# Slave.net
KiCad netlist of a schematic drawn in EAGLE
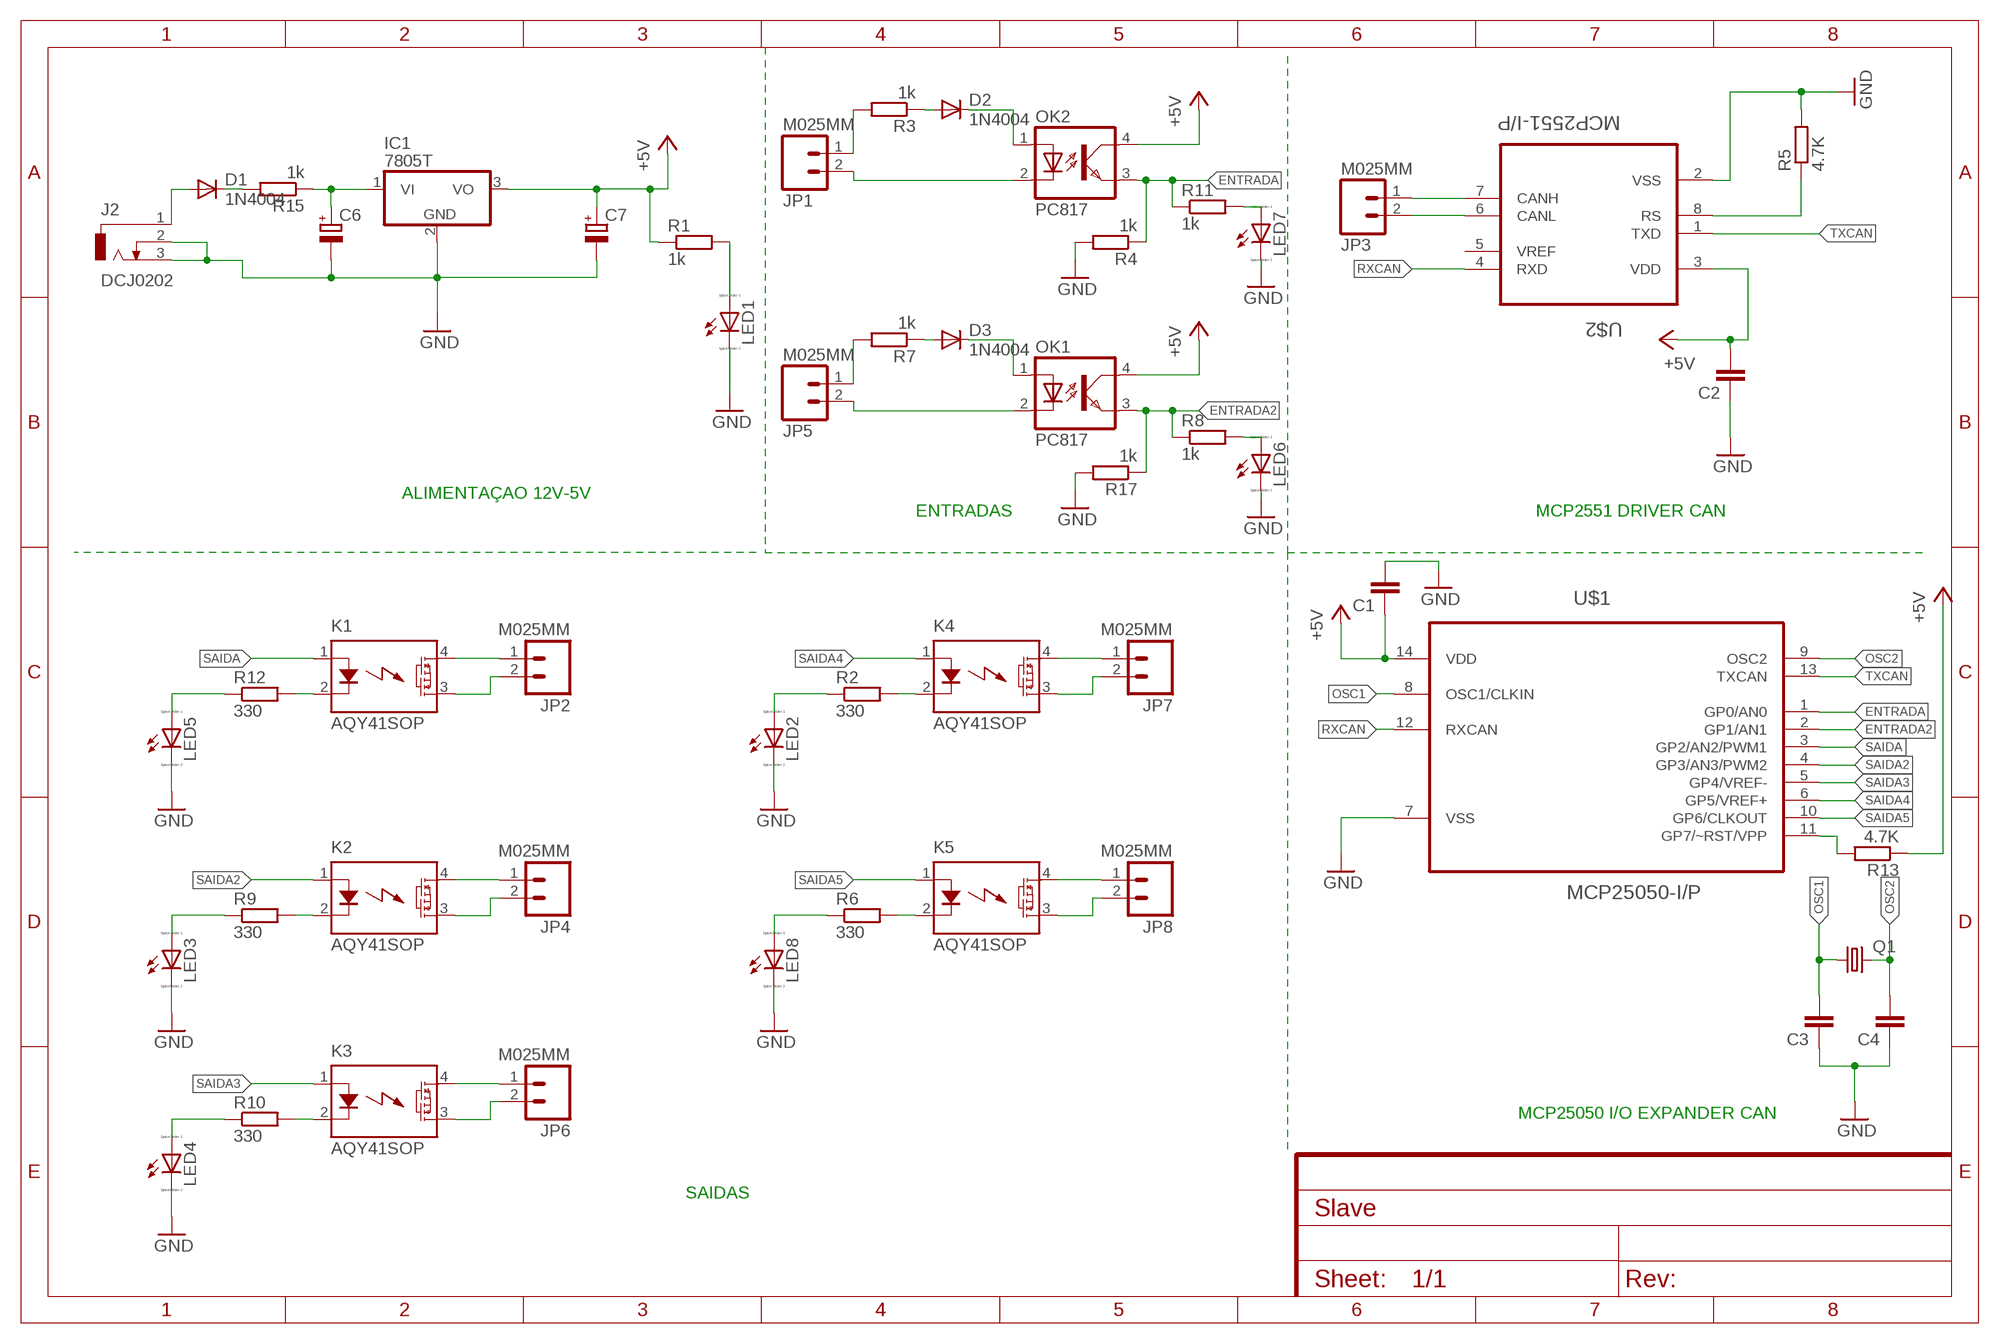
[diagram p0: schematic, sheet 1]

(export (version "E")
  (design (tool "Eeschema 10.0.6"))
  (components
    (comp (ref "C1")
      (value "C-EU025-025X050")
      (footprint "eagle-import:C025-025X050")
      (libsource (lib "eagle-import") (part "C-EU025-025X050"))
    )
    (comp (ref "C2")
      (value "C-EU025-025X050")
      (footprint "eagle-import:C025-025X050")
      (libsource (lib "eagle-import") (part "C-EU025-025X050"))
    )
    (comp (ref "C3")
      (value "CAP_")
      (footprint "eagle-import:AXIAL-5MM")
      (libsource (lib "eagle-import") (part "CAP_"))
    )
    (comp (ref "C4")
      (value "CAP_")
      (footprint "eagle-import:AXIAL-5MM")
      (libsource (lib "eagle-import") (part "CAP_"))
    )
    (comp (ref "C6")
      (value "CPOL-EUE2.5-6")
      (footprint "eagle-import:E2,5-6")
      (libsource (lib "eagle-import") (part "CPOL-EUE2.5-6"))
    )
    (comp (ref "C7")
      (value "CPOL-EUE2.5-6")
      (footprint "eagle-import:E2,5-6")
      (libsource (lib "eagle-import") (part "CPOL-EUE2.5-6"))
    )
    (comp (ref "D1")
      (value "1N4004")
      (footprint "eagle-import:DO41-10")
      (libsource (lib "eagle-import") (part "1N4004"))
    )
    (comp (ref "D2")
      (value "1N4004")
      (footprint "eagle-import:DO41-10")
      (libsource (lib "eagle-import") (part "1N4004"))
    )
    (comp (ref "D3")
      (value "1N4004")
      (footprint "eagle-import:DO41-10")
      (libsource (lib "eagle-import") (part "1N4004"))
    )
    (comp (ref "IC1")
      (value "7805T")
      (footprint "eagle-import:TO220H")
      (libsource (lib "eagle-import") (part "78T05"))
    )
    (comp (ref "J2")
      (value "DCJ0202")
      (footprint "eagle-import:DCJ0202")
      (libsource (lib "eagle-import") (part "DCJ0202"))
    )
    (comp (ref "JP1")
      (value "M025MM")
      (footprint "eagle-import:SCREWTERMINAL-5MM-2")
      (libsource (lib "eagle-import") (part "M025MM"))
    )
    (comp (ref "JP2")
      (value "M025MM")
      (footprint "eagle-import:SCREWTERMINAL-5MM-2")
      (libsource (lib "eagle-import") (part "M025MM"))
    )
    (comp (ref "JP3")
      (value "M025MM")
      (footprint "eagle-import:SCREWTERMINAL-5MM-2")
      (libsource (lib "eagle-import") (part "M025MM"))
    )
    (comp (ref "JP4")
      (value "M025MM")
      (footprint "eagle-import:SCREWTERMINAL-5MM-2")
      (libsource (lib "eagle-import") (part "M025MM"))
    )
    (comp (ref "JP5")
      (value "M025MM")
      (footprint "eagle-import:SCREWTERMINAL-5MM-2")
      (libsource (lib "eagle-import") (part "M025MM"))
    )
    (comp (ref "JP6")
      (value "M025MM")
      (footprint "eagle-import:SCREWTERMINAL-5MM-2")
      (libsource (lib "eagle-import") (part "M025MM"))
    )
    (comp (ref "JP7")
      (value "M025MM")
      (footprint "eagle-import:SCREWTERMINAL-5MM-2")
      (libsource (lib "eagle-import") (part "M025MM"))
    )
    (comp (ref "JP8")
      (value "M025MM")
      (footprint "eagle-import:SCREWTERMINAL-5MM-2")
      (libsource (lib "eagle-import") (part "M025MM"))
    )
    (comp (ref "K1")
      (value "AQY41SOP")
      (footprint "eagle-import:SOP04")
      (libsource (lib "eagle-import") (part "AQYSOP41"))
    )
    (comp (ref "K2")
      (value "AQY41SOP")
      (footprint "eagle-import:SOP04")
      (libsource (lib "eagle-import") (part "AQYSOP41"))
    )
    (comp (ref "K3")
      (value "AQY41SOP")
      (footprint "eagle-import:SOP04")
      (libsource (lib "eagle-import") (part "AQYSOP41"))
    )
    (comp (ref "K4")
      (value "AQY41SOP")
      (footprint "eagle-import:SOP04")
      (libsource (lib "eagle-import") (part "AQYSOP41"))
    )
    (comp (ref "K5")
      (value "AQY41SOP")
      (footprint "eagle-import:SOP04")
      (libsource (lib "eagle-import") (part "AQYSOP41"))
    )
    (comp (ref "LED1")
      (value "LED_ELD260")
      (footprint "eagle-import:LED_LD260")
      (libsource (lib "eagle-import") (part "LED_ELD260"))
    )
    (comp (ref "LED2")
      (value "LED_ELD260")
      (footprint "eagle-import:LED_LD260")
      (libsource (lib "eagle-import") (part "LED_ELD260"))
    )
    (comp (ref "LED3")
      (value "LED_ELD260")
      (footprint "eagle-import:LED_LD260")
      (libsource (lib "eagle-import") (part "LED_ELD260"))
    )
    (comp (ref "LED4")
      (value "LED_ELD260")
      (footprint "eagle-import:LED_LD260")
      (libsource (lib "eagle-import") (part "LED_ELD260"))
    )
    (comp (ref "LED5")
      (value "LED_ELD260")
      (footprint "eagle-import:LED_LD260")
      (libsource (lib "eagle-import") (part "LED_ELD260"))
    )
    (comp (ref "LED6")
      (value "LED_ELD260")
      (footprint "eagle-import:LED_LD260")
      (libsource (lib "eagle-import") (part "LED_ELD260"))
    )
    (comp (ref "LED7")
      (value "LED_ELD260")
      (footprint "eagle-import:LED_LD260")
      (libsource (lib "eagle-import") (part "LED_ELD260"))
    )
    (comp (ref "LED8")
      (value "LED_ELD260")
      (footprint "eagle-import:LED_LD260")
      (libsource (lib "eagle-import") (part "LED_ELD260"))
    )
    (comp (ref "OK1")
      (value "PC817")
      (footprint "eagle-import:DIL04")
      (fields (field (name "MPN") "PC817X4J000F"))
      (libsource (lib "eagle-import") (part "PC817"))
    )
    (comp (ref "OK2")
      (value "PC817")
      (footprint "eagle-import:DIL04")
      (fields (field (name "MPN") "PC817X4J000F"))
      (libsource (lib "eagle-import") (part "PC817"))
    )
    (comp (ref "Q1")
      (value "CRYTALHC49S")
      (footprint "eagle-import:HC49_S")
      (libsource (lib "eagle-import") (part "CRYTALHC49S"))
    )
    (comp (ref "R1")
      (value "1k")
      (footprint "eagle-import:0204_7")
      (libsource (lib "eagle-import") (part "R-EU_0204/7"))
    )
    (comp (ref "R2")
      (value "330")
      (footprint "eagle-import:0204_7")
      (libsource (lib "eagle-import") (part "R-EU_0204/7"))
    )
    (comp (ref "R3")
      (value "1k")
      (footprint "eagle-import:0204_7")
      (libsource (lib "eagle-import") (part "R-EU_0204/7"))
    )
    (comp (ref "R4")
      (value "1k")
      (footprint "eagle-import:0204_7")
      (libsource (lib "eagle-import") (part "R-EU_0204/7"))
    )
    (comp (ref "R5")
      (value "4.7K")
      (footprint "eagle-import:0204_7")
      (libsource (lib "eagle-import") (part "R-EU_0204/7"))
    )
    (comp (ref "R6")
      (value "330")
      (footprint "eagle-import:0204_7")
      (libsource (lib "eagle-import") (part "R-EU_0204/7"))
    )
    (comp (ref "R7")
      (value "1k")
      (footprint "eagle-import:0204_7")
      (libsource (lib "eagle-import") (part "R-EU_0204/7"))
    )
    (comp (ref "R8")
      (value "1k")
      (footprint "eagle-import:0204_7")
      (libsource (lib "eagle-import") (part "R-EU_0204/7"))
    )
    (comp (ref "R9")
      (value "330")
      (footprint "eagle-import:0204_7")
      (libsource (lib "eagle-import") (part "R-EU_0204/7"))
    )
    (comp (ref "R10")
      (value "330")
      (footprint "eagle-import:0204_7")
      (libsource (lib "eagle-import") (part "R-EU_0204/7"))
    )
    (comp (ref "R11")
      (value "1k")
      (footprint "eagle-import:0204_7")
      (libsource (lib "eagle-import") (part "R-EU_0204/7"))
    )
    (comp (ref "R12")
      (value "330")
      (footprint "eagle-import:0204_7")
      (libsource (lib "eagle-import") (part "R-EU_0204/7"))
    )
    (comp (ref "R13")
      (value "4.7K")
      (footprint "eagle-import:0204_7")
      (libsource (lib "eagle-import") (part "R-EU_0204/7"))
    )
    (comp (ref "R15")
      (value "1k")
      (footprint "eagle-import:0204_7")
      (libsource (lib "eagle-import") (part "R-EU_0204/7"))
    )
    (comp (ref "R17")
      (value "1k")
      (footprint "eagle-import:0204_7")
      (libsource (lib "eagle-import") (part "R-EU_0204/7"))
    )
    (comp (ref "U$1")
      (value "MCP25050-I/P")
      (footprint "eagle-import:DIP254P762X432-14")
      (libsource (lib "eagle-import") (part "MCP25050-I/P"))
    )
    (comp (ref "U$2")
      (value "MCP2551-I/P")
      (footprint "eagle-import:DIP254P762X432-8")
      (libsource (lib "eagle-import") (part "MCP2551-I/P"))
    )
  )
  (nets
    (net (code "1") (name "+5V") (class "Default")
      (node (ref "C1") (pin "1") (pinfunction "1_1") (pintype "passive"))
      (node (ref "C2") (pin "2") (pinfunction "2_2") (pintype "passive"))
      (node (ref "C7") (pin "+") (pinfunction "+_+") (pintype "passive"))
      (node (ref "IC1") (pin "3") (pinfunction "VO_3") (pintype "passive"))
      (node (ref "OK1") (pin "4") (pinfunction "COL_4") (pintype "passive"))
      (node (ref "OK2") (pin "4") (pinfunction "COL_4") (pintype "passive"))
      (node (ref "R1") (pin "1") (pinfunction "1_1") (pintype "passive"))
      (node (ref "R13") (pin "1") (pinfunction "1_1") (pintype "passive"))
      (node (ref "U$1") (pin "14") (pinfunction "VDD_14") (pintype "power_in"))
      (node (ref "U$2") (pin "3") (pinfunction "VDD_3") (pintype "power_in"))
    )
    (net (code "2") (name "ENTRADA") (class "Default")
      (node (ref "OK2") (pin "3") (pinfunction "EMIT_3") (pintype "passive"))
      (node (ref "R11") (pin "1") (pinfunction "1_1") (pintype "passive"))
      (node (ref "R4") (pin "1") (pinfunction "1_1") (pintype "passive"))
      (node (ref "U$1") (pin "1") (pinfunction "GP0/AN0_1") (pintype "bidirectional"))
    )
    (net (code "3") (name "ENTRADA2") (class "Default")
      (node (ref "OK1") (pin "3") (pinfunction "EMIT_3") (pintype "passive"))
      (node (ref "R17") (pin "1") (pinfunction "1_1") (pintype "passive"))
      (node (ref "R8") (pin "1") (pinfunction "1_1") (pintype "passive"))
      (node (ref "U$1") (pin "2") (pinfunction "GP1/AN1_2") (pintype "bidirectional"))
    )
    (net (code "4") (name "GND") (class "Default")
      (node (ref "C1") (pin "2") (pinfunction "2_2") (pintype "passive"))
      (node (ref "C2") (pin "1") (pinfunction "1_1") (pintype "passive"))
      (node (ref "C3") (pin "P$1") (pinfunction "1_P$1") (pintype "passive"))
      (node (ref "C4") (pin "P$1") (pinfunction "1_P$1") (pintype "passive"))
      (node (ref "C6") (pin "-") (pinfunction "-_-") (pintype "passive"))
      (node (ref "C7") (pin "-") (pinfunction "-_-") (pintype "passive"))
      (node (ref "IC1") (pin "2") (pinfunction "GND_2") (pintype "passive"))
      (node (ref "J2") (pin "2") (pinfunction "2_2") (pintype "passive"))
      (node (ref "J2") (pin "3") (pinfunction "3_3") (pintype "passive"))
      (node (ref "LED1") (pin "K") (pinfunction "C_K") (pintype "passive"))
      (node (ref "LED2") (pin "K") (pinfunction "C_K") (pintype "passive"))
      (node (ref "LED3") (pin "K") (pinfunction "C_K") (pintype "passive"))
      (node (ref "LED4") (pin "K") (pinfunction "C_K") (pintype "passive"))
      (node (ref "LED5") (pin "K") (pinfunction "C_K") (pintype "passive"))
      (node (ref "LED6") (pin "K") (pinfunction "C_K") (pintype "passive"))
      (node (ref "LED7") (pin "K") (pinfunction "C_K") (pintype "passive"))
      (node (ref "LED8") (pin "K") (pinfunction "C_K") (pintype "passive"))
      (node (ref "R17") (pin "2") (pinfunction "2_2") (pintype "passive"))
      (node (ref "R4") (pin "2") (pinfunction "2_2") (pintype "passive"))
      (node (ref "R5") (pin "2") (pinfunction "2_2") (pintype "passive"))
      (node (ref "U$1") (pin "7") (pinfunction "VSS_7") (pintype "passive"))
      (node (ref "U$2") (pin "2") (pinfunction "VSS_2") (pintype "power_in"))
    )
    (net (code "5") (name "Net-(D1-PadA)") (class "Default")
      (node (ref "D1") (pin "A") (pinfunction "A_A") (pintype "passive"))
      (node (ref "J2") (pin "1") (pinfunction "1_1") (pintype "passive"))
    )
    (net (code "6") (name "Net-(D1-PadC)") (class "Default")
      (node (ref "D1") (pin "C") (pinfunction "C_C") (pintype "passive"))
      (node (ref "R15") (pin "2") (pinfunction "2_2") (pintype "passive"))
    )
    (net (code "7") (name "Net-(D2-PadA)") (class "Default")
      (node (ref "D2") (pin "A") (pinfunction "A_A") (pintype "passive"))
      (node (ref "R3") (pin "1") (pinfunction "1_1") (pintype "passive"))
    )
    (net (code "8") (name "Net-(D3-PadA)") (class "Default")
      (node (ref "D3") (pin "A") (pinfunction "A_A") (pintype "passive"))
      (node (ref "R7") (pin "1") (pinfunction "1_1") (pintype "passive"))
    )
    (net (code "9") (name "Net-(IC1-VI)") (class "Default")
      (node (ref "C6") (pin "+") (pinfunction "+_+") (pintype "passive"))
      (node (ref "IC1") (pin "1") (pinfunction "VI_1") (pintype "input"))
      (node (ref "R15") (pin "1") (pinfunction "1_1") (pintype "passive"))
    )
    (net (code "10") (name "Net-(JP1-Pad1)") (class "Default")
      (node (ref "JP1") (pin "1") (pinfunction "1_1") (pintype "passive"))
      (node (ref "R3") (pin "2") (pinfunction "2_2") (pintype "passive"))
    )
    (net (code "11") (name "Net-(JP5-Pad1)") (class "Default")
      (node (ref "JP5") (pin "1") (pinfunction "1_1") (pintype "passive"))
      (node (ref "R7") (pin "2") (pinfunction "2_2") (pintype "passive"))
    )
    (net (code "12") (name "Net-(K1-DS1)") (class "Default")
      (node (ref "JP2") (pin "1") (pinfunction "1_1") (pintype "passive"))
      (node (ref "K1") (pin "4") (pinfunction "DS1_4") (pintype "passive"))
    )
    (net (code "13") (name "Net-(K1-DS2)") (class "Default")
      (node (ref "JP2") (pin "2") (pinfunction "2_2") (pintype "passive"))
      (node (ref "K1") (pin "3") (pinfunction "DS2_3") (pintype "passive"))
    )
    (net (code "14") (name "Net-(K1-K)") (class "Default")
      (node (ref "K1") (pin "2") (pinfunction "K_2") (pintype "passive"))
      (node (ref "R12") (pin "2") (pinfunction "2_2") (pintype "passive"))
    )
    (net (code "15") (name "Net-(K2-DS1)") (class "Default")
      (node (ref "JP4") (pin "1") (pinfunction "1_1") (pintype "passive"))
      (node (ref "K2") (pin "4") (pinfunction "DS1_4") (pintype "passive"))
    )
    (net (code "16") (name "Net-(K2-DS2)") (class "Default")
      (node (ref "JP4") (pin "2") (pinfunction "2_2") (pintype "passive"))
      (node (ref "K2") (pin "3") (pinfunction "DS2_3") (pintype "passive"))
    )
    (net (code "17") (name "Net-(K2-K)") (class "Default")
      (node (ref "K2") (pin "2") (pinfunction "K_2") (pintype "passive"))
      (node (ref "R9") (pin "2") (pinfunction "2_2") (pintype "passive"))
    )
    (net (code "18") (name "Net-(K3-DS1)") (class "Default")
      (node (ref "JP6") (pin "1") (pinfunction "1_1") (pintype "passive"))
      (node (ref "K3") (pin "4") (pinfunction "DS1_4") (pintype "passive"))
    )
    (net (code "19") (name "Net-(K3-DS2)") (class "Default")
      (node (ref "JP6") (pin "2") (pinfunction "2_2") (pintype "passive"))
      (node (ref "K3") (pin "3") (pinfunction "DS2_3") (pintype "passive"))
    )
    (net (code "20") (name "Net-(K3-K)") (class "Default")
      (node (ref "K3") (pin "2") (pinfunction "K_2") (pintype "passive"))
      (node (ref "R10") (pin "2") (pinfunction "2_2") (pintype "passive"))
    )
    (net (code "21") (name "Net-(K4-DS1)") (class "Default")
      (node (ref "JP7") (pin "1") (pinfunction "1_1") (pintype "passive"))
      (node (ref "K4") (pin "4") (pinfunction "DS1_4") (pintype "passive"))
    )
    (net (code "22") (name "Net-(K4-DS2)") (class "Default")
      (node (ref "JP7") (pin "2") (pinfunction "2_2") (pintype "passive"))
      (node (ref "K4") (pin "3") (pinfunction "DS2_3") (pintype "passive"))
    )
    (net (code "23") (name "Net-(K4-K)") (class "Default")
      (node (ref "K4") (pin "2") (pinfunction "K_2") (pintype "passive"))
      (node (ref "R2") (pin "2") (pinfunction "2_2") (pintype "passive"))
    )
    (net (code "24") (name "Net-(K5-DS1)") (class "Default")
      (node (ref "JP8") (pin "1") (pinfunction "1_1") (pintype "passive"))
      (node (ref "K5") (pin "4") (pinfunction "DS1_4") (pintype "passive"))
    )
    (net (code "25") (name "Net-(K5-DS2)") (class "Default")
      (node (ref "JP8") (pin "2") (pinfunction "2_2") (pintype "passive"))
      (node (ref "K5") (pin "3") (pinfunction "DS2_3") (pintype "passive"))
    )
    (net (code "26") (name "Net-(K5-K)") (class "Default")
      (node (ref "K5") (pin "2") (pinfunction "K_2") (pintype "passive"))
      (node (ref "R6") (pin "2") (pinfunction "2_2") (pintype "passive"))
    )
    (net (code "27") (name "Net-(LED1-PadA)") (class "Default")
      (node (ref "LED1") (pin "A") (pinfunction "A_A") (pintype "passive"))
      (node (ref "R1") (pin "2") (pinfunction "2_2") (pintype "passive"))
    )
    (net (code "28") (name "Net-(LED2-PadA)") (class "Default")
      (node (ref "LED2") (pin "A") (pinfunction "A_A") (pintype "passive"))
      (node (ref "R2") (pin "1") (pinfunction "1_1") (pintype "passive"))
    )
    (net (code "29") (name "Net-(LED3-PadA)") (class "Default")
      (node (ref "LED3") (pin "A") (pinfunction "A_A") (pintype "passive"))
      (node (ref "R9") (pin "1") (pinfunction "1_1") (pintype "passive"))
    )
    (net (code "30") (name "Net-(LED4-PadA)") (class "Default")
      (node (ref "LED4") (pin "A") (pinfunction "A_A") (pintype "passive"))
      (node (ref "R10") (pin "1") (pinfunction "1_1") (pintype "passive"))
    )
    (net (code "31") (name "Net-(LED5-PadA)") (class "Default")
      (node (ref "LED5") (pin "A") (pinfunction "A_A") (pintype "passive"))
      (node (ref "R12") (pin "1") (pinfunction "1_1") (pintype "passive"))
    )
    (net (code "32") (name "Net-(LED6-PadA)") (class "Default")
      (node (ref "LED6") (pin "A") (pinfunction "A_A") (pintype "passive"))
      (node (ref "R8") (pin "2") (pinfunction "2_2") (pintype "passive"))
    )
    (net (code "33") (name "Net-(LED7-PadA)") (class "Default")
      (node (ref "LED7") (pin "A") (pinfunction "A_A") (pintype "passive"))
      (node (ref "R11") (pin "2") (pinfunction "2_2") (pintype "passive"))
    )
    (net (code "34") (name "Net-(LED8-PadA)") (class "Default")
      (node (ref "LED8") (pin "A") (pinfunction "A_A") (pintype "passive"))
      (node (ref "R6") (pin "1") (pinfunction "1_1") (pintype "passive"))
    )
    (net (code "35") (name "Net-(OK1-A)") (class "Default")
      (node (ref "D3") (pin "C") (pinfunction "C_C") (pintype "passive"))
      (node (ref "OK1") (pin "1") (pinfunction "A_1") (pintype "passive"))
    )
    (net (code "36") (name "Net-(OK1-C)") (class "Default")
      (node (ref "JP5") (pin "2") (pinfunction "2_2") (pintype "passive"))
      (node (ref "OK1") (pin "2") (pinfunction "C_2") (pintype "passive"))
    )
    (net (code "37") (name "Net-(OK2-A)") (class "Default")
      (node (ref "D2") (pin "C") (pinfunction "C_C") (pintype "passive"))
      (node (ref "OK2") (pin "1") (pinfunction "A_1") (pintype "passive"))
    )
    (net (code "38") (name "Net-(OK2-C)") (class "Default")
      (node (ref "JP1") (pin "2") (pinfunction "2_2") (pintype "passive"))
      (node (ref "OK2") (pin "2") (pinfunction "C_2") (pintype "passive"))
    )
    (net (code "39") (name "Net-(U$1-GP7{slash}~{RST{slash}VPP})") (class "Default")
      (node (ref "R13") (pin "2") (pinfunction "2_2") (pintype "passive"))
      (node (ref "U$1") (pin "11") (pinfunction "GP7/~{RST/VPP}_11") (pintype "bidirectional"))
    )
    (net (code "40") (name "Net-(U$2-CANH)") (class "Default")
      (node (ref "JP3") (pin "1") (pinfunction "1_1") (pintype "passive"))
      (node (ref "U$2") (pin "7") (pinfunction "CANH_7") (pintype "bidirectional"))
    )
    (net (code "41") (name "Net-(U$2-CANL)") (class "Default")
      (node (ref "JP3") (pin "2") (pinfunction "2_2") (pintype "passive"))
      (node (ref "U$2") (pin "6") (pinfunction "CANL_6") (pintype "bidirectional"))
    )
    (net (code "42") (name "Net-(U$2-RS)") (class "Default")
      (node (ref "R5") (pin "1") (pinfunction "1_1") (pintype "passive"))
      (node (ref "U$2") (pin "8") (pinfunction "RS_8") (pintype "input"))
    )
    (net (code "43") (name "OSC1") (class "Default")
      (node (ref "C3") (pin "P$2") (pinfunction "2_P$2") (pintype "passive"))
      (node (ref "Q1") (pin "1") (pinfunction "1_1") (pintype "passive"))
      (node (ref "U$1") (pin "8") (pinfunction "OSC1/CLKIN_8") (pintype "input"))
    )
    (net (code "44") (name "OSC2") (class "Default")
      (node (ref "C4") (pin "P$2") (pinfunction "2_P$2") (pintype "passive"))
      (node (ref "Q1") (pin "2") (pinfunction "2_2") (pintype "passive"))
      (node (ref "U$1") (pin "9") (pinfunction "OSC2_9") (pintype "output"))
    )
    (net (code "45") (name "RXCAN") (class "Default")
      (node (ref "U$1") (pin "12") (pinfunction "RXCAN_12") (pintype "input"))
      (node (ref "U$2") (pin "4") (pinfunction "RXD_4") (pintype "output"))
    )
    (net (code "46") (name "SAIDA") (class "Default")
      (node (ref "K1") (pin "1") (pinfunction "A_1") (pintype "passive"))
      (node (ref "U$1") (pin "3") (pinfunction "GP2/AN2/PWM1_3") (pintype "bidirectional"))
    )
    (net (code "47") (name "SAIDA2") (class "Default")
      (node (ref "K2") (pin "1") (pinfunction "A_1") (pintype "passive"))
      (node (ref "U$1") (pin "4") (pinfunction "GP3/AN3/PWM2_4") (pintype "bidirectional"))
    )
    (net (code "48") (name "SAIDA3") (class "Default")
      (node (ref "K3") (pin "1") (pinfunction "A_1") (pintype "passive"))
      (node (ref "U$1") (pin "5") (pinfunction "GP4/VREF-_5") (pintype "bidirectional"))
    )
    (net (code "49") (name "SAIDA4") (class "Default")
      (node (ref "K4") (pin "1") (pinfunction "A_1") (pintype "passive"))
      (node (ref "U$1") (pin "6") (pinfunction "GP5/VREF+_6") (pintype "bidirectional"))
    )
    (net (code "50") (name "SAIDA5") (class "Default")
      (node (ref "K5") (pin "1") (pinfunction "A_1") (pintype "passive"))
      (node (ref "U$1") (pin "10") (pinfunction "GP6/CLKOUT_10") (pintype "bidirectional"))
    )
    (net (code "51") (name "TXCAN") (class "Default")
      (node (ref "U$1") (pin "13") (pinfunction "TXCAN_13") (pintype "output"))
      (node (ref "U$2") (pin "1") (pinfunction "TXD_1") (pintype "input"))
    )
    (net (code "52") (name "unconnected-(U$2-VREF-Pad5)") (class "Default")
      (node (ref "U$2") (pin "5") (pinfunction "VREF_5") (pintype "output"))
    )
  )
)
